# Kobold_--_ATtiny85_and_DRV8830_Combo_--_.net
KiCad netlist of a schematic drawn in EAGLE
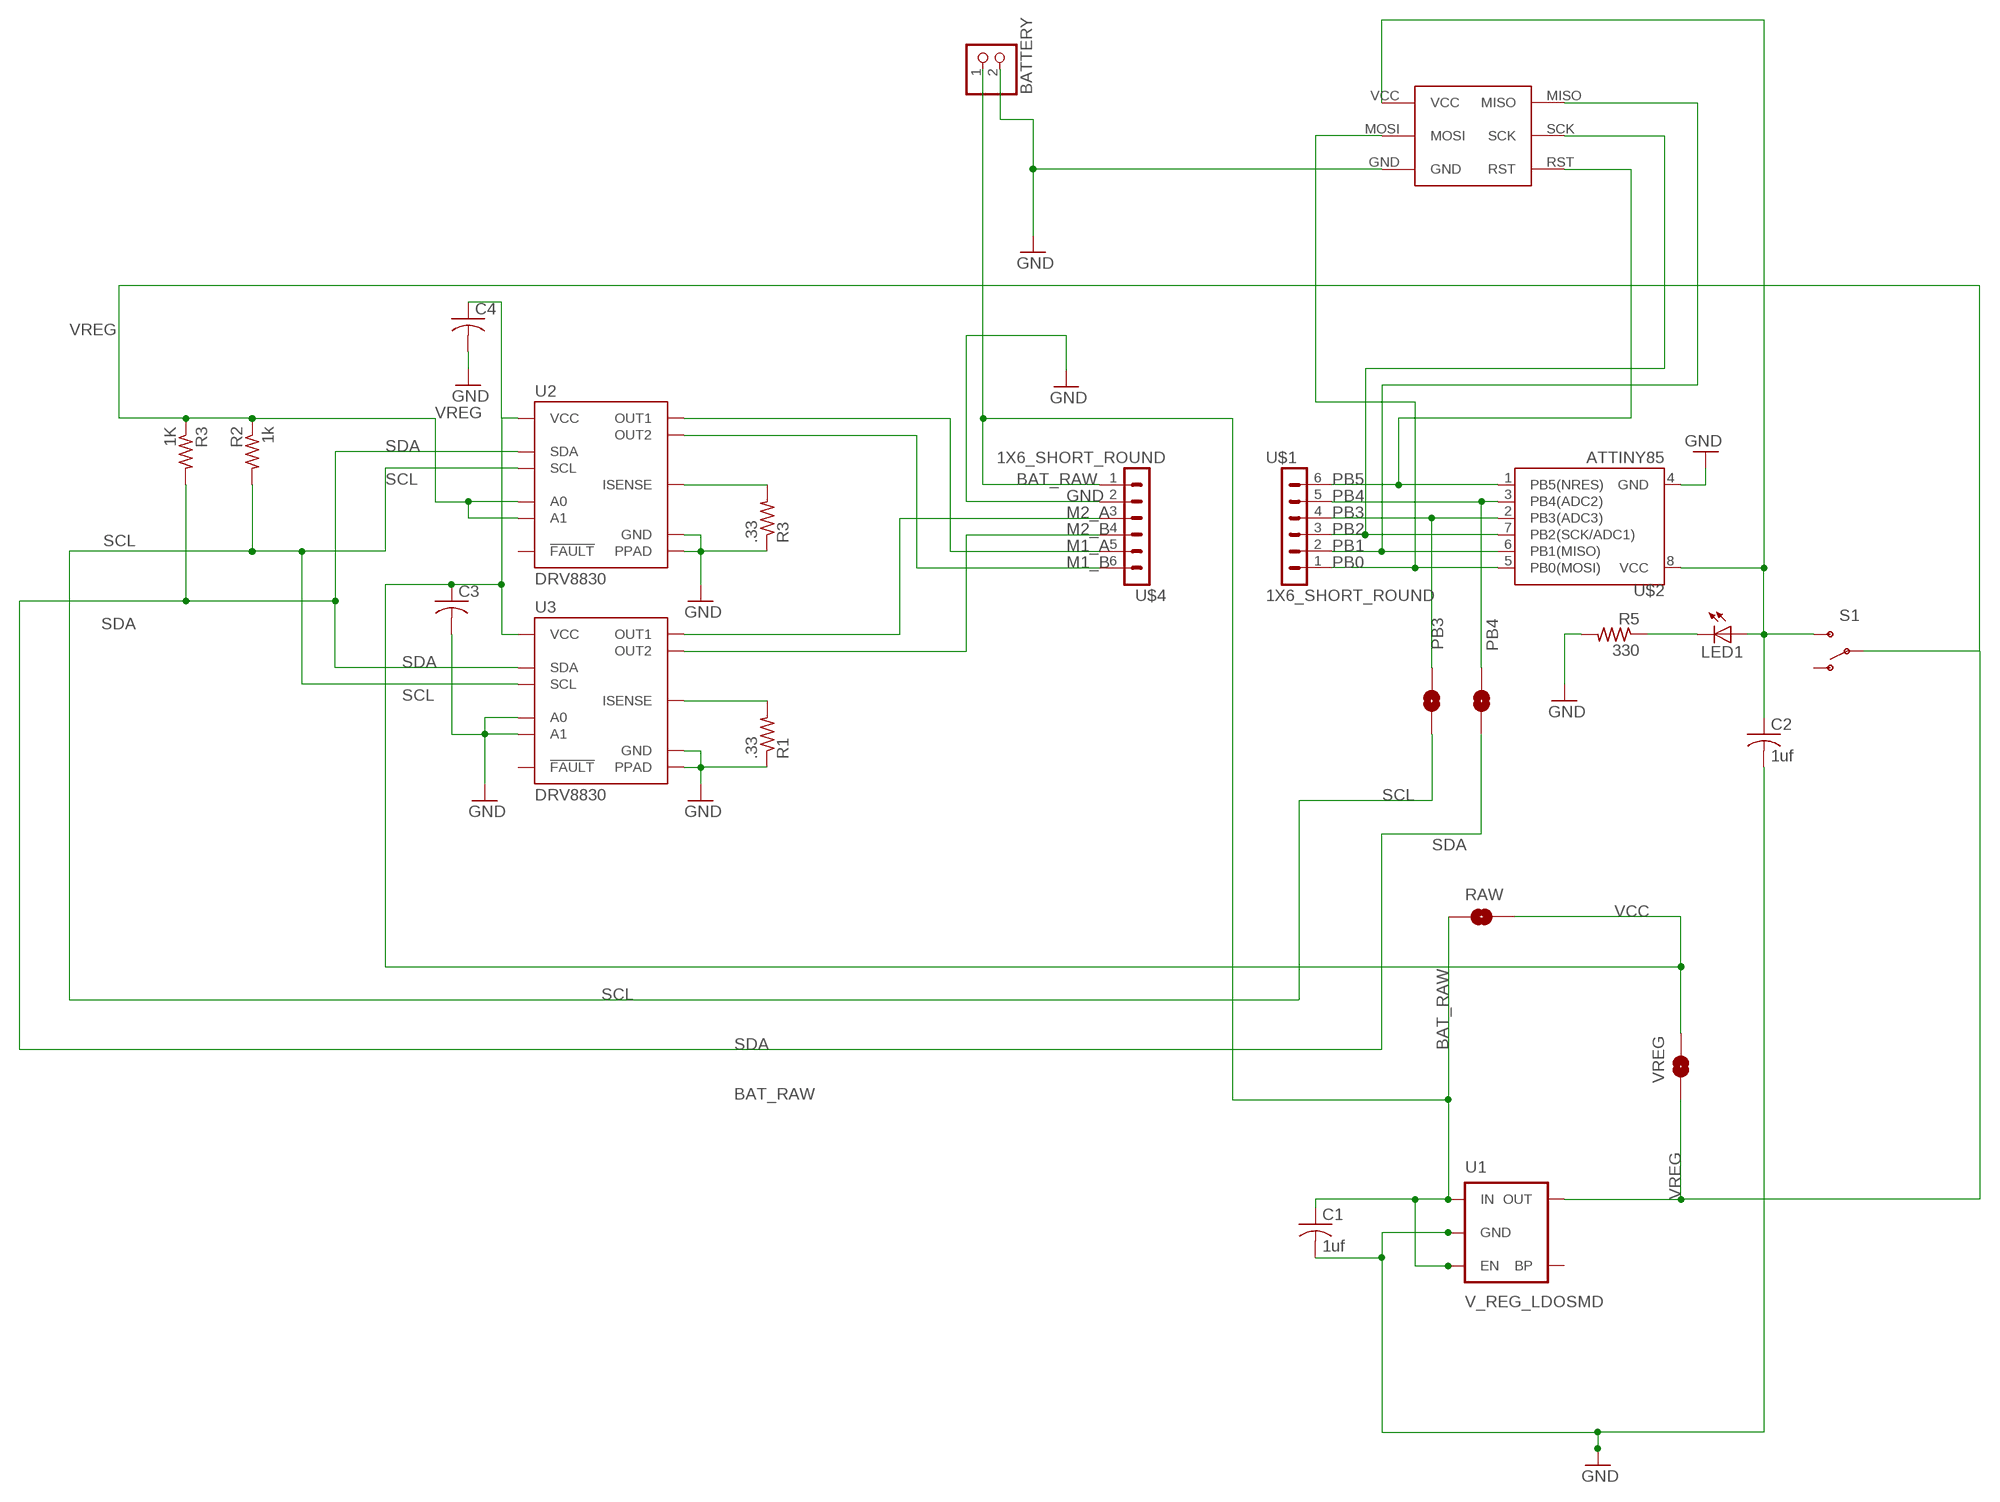
[diagram p0: schematic, sheet 1]

(export (version "E")
  (design (tool "Eeschema 10.0.6"))
  (components
    (comp (ref "1K")
      (value "R3")
      (footprint "eagle-import:R0402")
      (libsource (lib "eagle-import") (part "R-US_R0402"))
    )
    (comp (ref "BATTERY")
      (value "JST_2PIN-THM")
      (footprint "eagle-import:JST-PH-2-THM")
      (libsource (lib "eagle-import") (part "JST_2PIN-THM"))
    )
    (comp (ref "C1")
      (value "1uf")
      (footprint "eagle-import:C0402")
      (libsource (lib "eagle-import") (part "C-USC0402"))
    )
    (comp (ref "C2")
      (value "1uf")
      (footprint "eagle-import:C0402")
      (libsource (lib "eagle-import") (part "C-USC0402"))
    )
    (comp (ref "C3")
      (value "C-USC0402")
      (footprint "eagle-import:C0402")
      (libsource (lib "eagle-import") (part "C-USC0402"))
    )
    (comp (ref "C4")
      (value "C-USC0402")
      (footprint "eagle-import:C0402")
      (libsource (lib "eagle-import") (part "C-USC0402"))
    )
    (comp (ref "LED1")
      (value "LEDCHIP-LED0603")
      (footprint "eagle-import:CHIP-LED0603")
      (libsource (lib "eagle-import") (part "LEDCHIP-LED0603"))
    )
    (comp (ref "R1")
      (value ".33")
      (footprint "eagle-import:R0402")
      (libsource (lib "eagle-import") (part "R-US_R0402"))
    )
    (comp (ref "R2")
      (value "1k")
      (footprint "eagle-import:R0402")
      (libsource (lib "eagle-import") (part "R-US_R0402"))
    )
    (comp (ref "R3")
      (value ".33")
      (footprint "eagle-import:R0402")
      (libsource (lib "eagle-import") (part "R-US_R0402"))
    )
    (comp (ref "R5")
      (value "330")
      (footprint "eagle-import:R0402")
      (libsource (lib "eagle-import") (part "R-US_R0402"))
    )
    (comp (ref "RAW")
      (value "SOLDERJUMPERNO")
      (footprint "eagle-import:SJ_2S-NO")
      (libsource (lib "eagle-import") (part "SOLDERJUMPERNO"))
    )
    (comp (ref "S1")
      (value "SWITCH-SPDT-SMD-A")
      (footprint "eagle-import:SWITCH-SPST-SMD-A")
      (libsource (lib "eagle-import") (part "SWITCH-SPDT-SMD-A"))
    )
    (comp (ref "SJ6")
      (value "SOLDERJUMPERNO")
      (footprint "eagle-import:SJ_2S-NO")
      (libsource (lib "eagle-import") (part "SOLDERJUMPERNO"))
    )
    (comp (ref "SJ7")
      (value "SOLDERJUMPERNO")
      (footprint "eagle-import:SJ_2S-NO")
      (libsource (lib "eagle-import") (part "SOLDERJUMPERNO"))
    )
    (comp (ref "U$1")
      (value "1X6_SHORT_ROUND")
      (footprint "eagle-import:1X6_SHORT_ROUND")
      (libsource (lib "eagle-import") (part "1X6_SHORT_ROUND"))
    )
    (comp (ref "U$2")
      (value "ATTINY85")
      (footprint "eagle-import:SO08-EIAJ")
      (libsource (lib "eagle-import") (part "ATTINY45"))
    )
    (comp (ref "U$4")
      (value "1X6_SHORT_ROUND")
      (footprint "eagle-import:1X6_SHORT_ROUND")
      (libsource (lib "eagle-import") (part "1X6_SHORT_ROUND"))
    )
    (comp (ref "U$5")
      (value "POGO_PIN_SPI_PAD")
      (footprint "eagle-import:POGO_PIN_SPI_PAD")
      (libsource (lib "eagle-import") (part "POGO_PIN_SPI_PAD"))
    )
    (comp (ref "U1")
      (value "V_REG_LDOSMD")
      (footprint "eagle-import:SOT23-5")
      (libsource (lib "eagle-import") (part "V_REG_LDOSMD"))
    )
    (comp (ref "U2")
      (value "DRV8830")
      (footprint "eagle-import:MSOP-10-GNDPAD")
      (libsource (lib "eagle-import") (part "DRV8830"))
    )
    (comp (ref "U3")
      (value "DRV8830")
      (footprint "eagle-import:MSOP-10-GNDPAD")
      (libsource (lib "eagle-import") (part "DRV8830"))
    )
    (comp (ref "VREG")
      (value "SOLDERJUMPERNO")
      (footprint "eagle-import:SJ_2S-NO")
      (libsource (lib "eagle-import") (part "SOLDERJUMPERNO"))
    )
  )
  (nets
    (net (code "1") (name "/BAT_RAW") (class "Default")
      (node (ref "BATTERY") (pin "1") (pinfunction "2_1") (pintype "passive"))
      (node (ref "C1") (pin "1") (pinfunction "1_1") (pintype "passive"))
      (node (ref "RAW") (pin "1") (pinfunction "1_1") (pintype "passive"))
      (node (ref "U$4") (pin "1") (pinfunction "1_1") (pintype "passive"))
      (node (ref "U1") (pin "1") (pinfunction "IN_1") (pintype "input"))
      (node (ref "U1") (pin "3") (pinfunction "EN_3") (pintype "input"))
    )
    (net (code "2") (name "/M1_A") (class "Default")
      (node (ref "U$4") (pin "5") (pinfunction "5_5") (pintype "passive"))
      (node (ref "U2") (pin "3") (pinfunction "OUT1_3") (pintype "power_in"))
    )
    (net (code "3") (name "/M1_B") (class "Default")
      (node (ref "U$4") (pin "6") (pinfunction "6_6") (pintype "passive"))
      (node (ref "U2") (pin "1") (pinfunction "OUT2_1") (pintype "power_in"))
    )
    (net (code "4") (name "/M2_A") (class "Default")
      (node (ref "U$4") (pin "3") (pinfunction "3_3") (pintype "passive"))
      (node (ref "U3") (pin "3") (pinfunction "OUT1_3") (pintype "power_in"))
    )
    (net (code "5") (name "/M2_B") (class "Default")
      (node (ref "U$4") (pin "4") (pinfunction "4_4") (pintype "passive"))
      (node (ref "U3") (pin "1") (pinfunction "OUT2_1") (pintype "power_in"))
    )
    (net (code "6") (name "/PB0") (class "Default")
      (node (ref "U$1") (pin "1") (pinfunction "1_1") (pintype "passive"))
      (node (ref "U$2") (pin "5") (pinfunction "PB0(MOSI)_5") (pintype "bidirectional"))
      (node (ref "U$5") (pin "MOSI") (pinfunction "MOSI_MOSI") (pintype "bidirectional"))
    )
    (net (code "7") (name "/PB1") (class "Default")
      (node (ref "U$1") (pin "2") (pinfunction "2_2") (pintype "passive"))
      (node (ref "U$2") (pin "6") (pinfunction "PB1(MISO)_6") (pintype "bidirectional"))
      (node (ref "U$5") (pin "MISO") (pinfunction "MISO_MISO") (pintype "bidirectional"))
    )
    (net (code "8") (name "/PB2") (class "Default")
      (node (ref "U$1") (pin "3") (pinfunction "3_3") (pintype "passive"))
      (node (ref "U$2") (pin "7") (pinfunction "PB2(SCK/ADC1)_7") (pintype "bidirectional"))
      (node (ref "U$5") (pin "SCK") (pinfunction "SCK_SCK") (pintype "bidirectional"))
    )
    (net (code "9") (name "/PB3") (class "Default")
      (node (ref "SJ7") (pin "2") (pinfunction "2_2") (pintype "passive"))
      (node (ref "U$1") (pin "4") (pinfunction "4_4") (pintype "passive"))
      (node (ref "U$2") (pin "2") (pinfunction "PB3(ADC3)_2") (pintype "bidirectional"))
    )
    (net (code "10") (name "/PB4") (class "Default")
      (node (ref "SJ6") (pin "2") (pinfunction "2_2") (pintype "passive"))
      (node (ref "U$1") (pin "5") (pinfunction "5_5") (pintype "passive"))
      (node (ref "U$2") (pin "3") (pinfunction "PB4(ADC2)_3") (pintype "bidirectional"))
    )
    (net (code "11") (name "/PB5") (class "Default")
      (node (ref "U$1") (pin "6") (pinfunction "6_6") (pintype "passive"))
      (node (ref "U$2") (pin "1") (pinfunction "PB5(NRES)_1") (pintype "bidirectional"))
      (node (ref "U$5") (pin "RST") (pinfunction "RST_RST") (pintype "bidirectional"))
    )
    (net (code "12") (name "/SCL") (class "Default")
      (node (ref "R2") (pin "2") (pinfunction "2_2") (pintype "passive"))
      (node (ref "SJ7") (pin "1") (pinfunction "1_1") (pintype "passive"))
      (node (ref "U2") (pin "10") (pinfunction "SCL_10") (pintype "input"))
      (node (ref "U3") (pin "10") (pinfunction "SCL_10") (pintype "input"))
    )
    (net (code "13") (name "/SDA") (class "Default")
      (node (ref "1K") (pin "2") (pinfunction "2_2") (pintype "passive"))
      (node (ref "SJ6") (pin "1") (pinfunction "1_1") (pintype "passive"))
      (node (ref "U2") (pin "9") (pinfunction "SDA_9") (pintype "bidirectional"))
      (node (ref "U3") (pin "9") (pinfunction "SDA_9") (pintype "bidirectional"))
    )
    (net (code "14") (name "/VCC") (class "Default")
      (node (ref "C3") (pin "1") (pinfunction "1_1") (pintype "passive"))
      (node (ref "C4") (pin "1") (pinfunction "1_1") (pintype "passive"))
      (node (ref "RAW") (pin "2") (pinfunction "2_2") (pintype "passive"))
      (node (ref "U2") (pin "4") (pinfunction "VCC_4") (pintype "power_in"))
      (node (ref "U3") (pin "4") (pinfunction "VCC_4") (pintype "power_in"))
      (node (ref "VREG") (pin "2") (pinfunction "2_2") (pintype "passive"))
    )
    (net (code "15") (name "/VREG") (class "Default")
      (node (ref "1K") (pin "1") (pinfunction "1_1") (pintype "passive"))
      (node (ref "R2") (pin "1") (pinfunction "1_1") (pintype "passive"))
      (node (ref "S1") (pin "2") (pinfunction "P_2") (pintype "passive"))
      (node (ref "U1") (pin "5") (pinfunction "OUT_5") (pintype "passive"))
      (node (ref "U2") (pin "7") (pinfunction "A0_7") (pintype "input"))
      (node (ref "U2") (pin "8") (pinfunction "A1_8") (pintype "input"))
      (node (ref "VREG") (pin "1") (pinfunction "1_1") (pintype "passive"))
    )
    (net (code "16") (name "GND") (class "Default")
      (node (ref "BATTERY") (pin "2") (pinfunction "1_2") (pintype "passive"))
      (node (ref "C1") (pin "2") (pinfunction "2_2") (pintype "passive"))
      (node (ref "C2") (pin "2") (pinfunction "2_2") (pintype "passive"))
      (node (ref "C3") (pin "2") (pinfunction "2_2") (pintype "passive"))
      (node (ref "C4") (pin "2") (pinfunction "2_2") (pintype "passive"))
      (node (ref "R1") (pin "1") (pinfunction "1_1") (pintype "passive"))
      (node (ref "R3") (pin "1") (pinfunction "1_1") (pintype "passive"))
      (node (ref "R5") (pin "2") (pinfunction "2_2") (pintype "passive"))
      (node (ref "U$2") (pin "4") (pinfunction "GND_4") (pintype "bidirectional"))
      (node (ref "U$4") (pin "2") (pinfunction "2_2") (pintype "passive"))
      (node (ref "U$5") (pin "GND") (pinfunction "GND_GND") (pintype "bidirectional"))
      (node (ref "U1") (pin "2") (pinfunction "GND_2") (pintype "input"))
      (node (ref "U2") (pin "5") (pinfunction "GND_5") (pintype "power_in"))
      (node (ref "U2") (pin "GND") (pinfunction "PPAD_GND") (pintype "power_in"))
      (node (ref "U3") (pin "5") (pinfunction "GND_5") (pintype "power_in"))
      (node (ref "U3") (pin "7") (pinfunction "A0_7") (pintype "input"))
      (node (ref "U3") (pin "8") (pinfunction "A1_8") (pintype "input"))
      (node (ref "U3") (pin "GND") (pinfunction "PPAD_GND") (pintype "power_in"))
    )
    (net (code "17") (name "Net-(LED1-PadC)") (class "Default")
      (node (ref "LED1") (pin "C") (pinfunction "C_C") (pintype "passive"))
      (node (ref "R5") (pin "1") (pinfunction "1_1") (pintype "passive"))
    )
    (net (code "18") (name "Net-(S1-S)") (class "Default")
      (node (ref "C2") (pin "1") (pinfunction "1_1") (pintype "passive"))
      (node (ref "LED1") (pin "A") (pinfunction "A_A") (pintype "passive"))
      (node (ref "S1") (pin "3") (pinfunction "S_3") (pintype "passive"))
      (node (ref "U$2") (pin "8") (pinfunction "VCC_8") (pintype "bidirectional"))
      (node (ref "U$5") (pin "VCC") (pinfunction "VCC_VCC") (pintype "bidirectional"))
    )
    (net (code "19") (name "Net-(U2-ISENSE)") (class "Default")
      (node (ref "R3") (pin "2") (pinfunction "2_2") (pintype "passive"))
      (node (ref "U2") (pin "2") (pinfunction "ISENSE_2") (pintype "bidirectional"))
    )
    (net (code "20") (name "Net-(U3-ISENSE)") (class "Default")
      (node (ref "R1") (pin "2") (pinfunction "2_2") (pintype "passive"))
      (node (ref "U3") (pin "2") (pinfunction "ISENSE_2") (pintype "bidirectional"))
    )
    (net (code "21") (name "unconnected-(S1-O-Pad1)") (class "Default")
      (node (ref "S1") (pin "1") (pinfunction "O_1") (pintype "passive"))
    )
    (net (code "22") (name "unconnected-(U1-BP-Pad4)") (class "Default")
      (node (ref "U1") (pin "4") (pinfunction "BP_4") (pintype "input"))
    )
    (net (code "23") (name "unconnected-(U2-~{FAULT}-Pad6)") (class "Default")
      (node (ref "U2") (pin "6") (pinfunction "~{FAULT}_6") (pintype "output"))
    )
    (net (code "24") (name "unconnected-(U3-~{FAULT}-Pad6)") (class "Default")
      (node (ref "U3") (pin "6") (pinfunction "~{FAULT}_6") (pintype "output"))
    )
  )
)
